# spi-adapter.net
KiCad netlist of a schematic drawn in EAGLE
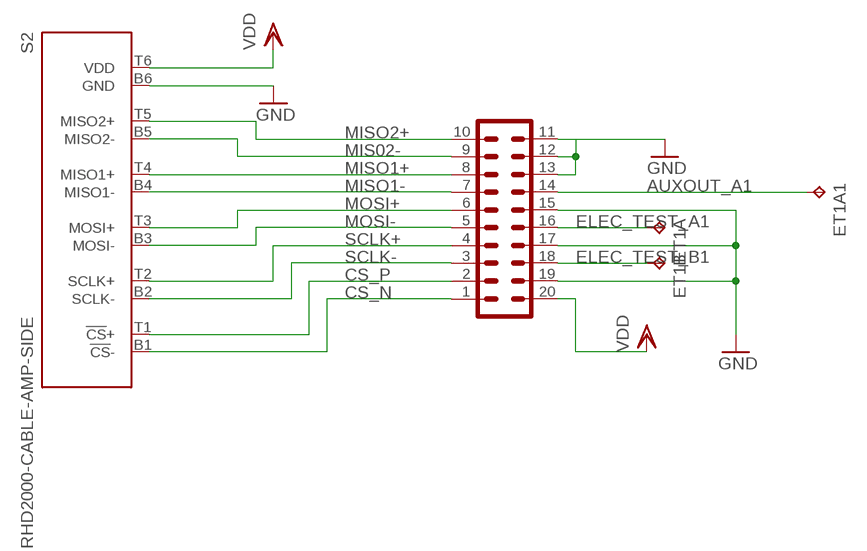
[diagram p0: schematic, sheet 1]

(export (version "E")
  (design (tool "Eeschema 10.0.6"))
  (components
    (comp (ref "ET1A")
      (value "TPPAD1-13")
      (footprint "eagle-import:P1-13")
      (libsource (lib "eagle-import") (part "TPPAD1-13"))
    )
    (comp (ref "ET1A1")
      (value "TPPAD1-13")
      (footprint "eagle-import:P1-13")
      (libsource (lib "eagle-import") (part "TPPAD1-13"))
    )
    (comp (ref "ET1B")
      (value "TPPAD1-13")
      (footprint "eagle-import:P1-13")
      (libsource (lib "eagle-import") (part "TPPAD1-13"))
    )
    (comp (ref "HS1")
      (value "JMD20-V")
      (footprint "eagle-import:JMD20-V")
      (libsource (lib "eagle-import") (part "PINHD-2X10_JMD20-V"))
    )
    (comp (ref "S2")
      (value "RHD2000-CABLE-AMP-SIDE")
      (footprint "eagle-import:OMNETICS_PZN-12-AA")
      (libsource (lib "eagle-import") (part "RHD2000-CABLE-AMP-SIDE"))
    )
  )
  (nets
    (net (code "1") (name "/AUXOUT_A1") (class "Default")
      (node (ref "ET1A1") (pin "TP") (pinfunction "TP_TP") (pintype "input"))
      (node (ref "HS1") (pin "14") (pinfunction "14_14") (pintype "bidirectional"))
    )
    (net (code "2") (name "/CS_N") (class "Default")
      (node (ref "HS1") (pin "1") (pinfunction "1_1") (pintype "bidirectional"))
      (node (ref "S2") (pin "B1") (pinfunction "~{CS}-_B1") (pintype "bidirectional"))
    )
    (net (code "3") (name "/CS_P") (class "Default")
      (node (ref "HS1") (pin "2") (pinfunction "2_2") (pintype "bidirectional"))
      (node (ref "S2") (pin "T1") (pinfunction "~{CS}+_T1") (pintype "bidirectional"))
    )
    (net (code "4") (name "/ELEC_TEST_A1") (class "Default")
      (node (ref "ET1A") (pin "TP") (pinfunction "TP_TP") (pintype "input"))
      (node (ref "HS1") (pin "16") (pinfunction "16_16") (pintype "bidirectional"))
    )
    (net (code "5") (name "/ELEC_TEST_B1") (class "Default")
      (node (ref "ET1B") (pin "TP") (pinfunction "TP_TP") (pintype "input"))
      (node (ref "HS1") (pin "18") (pinfunction "18_18") (pintype "bidirectional"))
    )
    (net (code "6") (name "/MIS02-") (class "Default")
      (node (ref "HS1") (pin "9") (pinfunction "9_9") (pintype "bidirectional"))
      (node (ref "S2") (pin "B5") (pinfunction "MISO2-_B5") (pintype "bidirectional"))
    )
    (net (code "7") (name "/MISO1+") (class "Default")
      (node (ref "HS1") (pin "8") (pinfunction "8_8") (pintype "bidirectional"))
      (node (ref "S2") (pin "T4") (pinfunction "MISO1+_T4") (pintype "bidirectional"))
    )
    (net (code "8") (name "/MISO1-") (class "Default")
      (node (ref "HS1") (pin "7") (pinfunction "7_7") (pintype "bidirectional"))
      (node (ref "S2") (pin "B4") (pinfunction "MISO1-_B4") (pintype "bidirectional"))
    )
    (net (code "9") (name "/MISO2+") (class "Default")
      (node (ref "HS1") (pin "10") (pinfunction "10_10") (pintype "bidirectional"))
      (node (ref "S2") (pin "T5") (pinfunction "MISO2+_T5") (pintype "bidirectional"))
    )
    (net (code "10") (name "/MOSI+") (class "Default")
      (node (ref "HS1") (pin "6") (pinfunction "6_6") (pintype "bidirectional"))
      (node (ref "S2") (pin "T3") (pinfunction "MOSI+_T3") (pintype "bidirectional"))
    )
    (net (code "11") (name "/MOSI-") (class "Default")
      (node (ref "HS1") (pin "5") (pinfunction "5_5") (pintype "bidirectional"))
      (node (ref "S2") (pin "B3") (pinfunction "MOSI-_B3") (pintype "bidirectional"))
    )
    (net (code "12") (name "/SCLK+") (class "Default")
      (node (ref "HS1") (pin "4") (pinfunction "4_4") (pintype "bidirectional"))
      (node (ref "S2") (pin "T2") (pinfunction "SCLK+_T2") (pintype "bidirectional"))
    )
    (net (code "13") (name "/SCLK-") (class "Default")
      (node (ref "HS1") (pin "3") (pinfunction "3_3") (pintype "bidirectional"))
      (node (ref "S2") (pin "B2") (pinfunction "SCLK-_B2") (pintype "bidirectional"))
    )
    (net (code "14") (name "GND") (class "Default")
      (node (ref "HS1") (pin "11") (pinfunction "11_11") (pintype "bidirectional"))
      (node (ref "HS1") (pin "12") (pinfunction "12_12") (pintype "bidirectional"))
      (node (ref "HS1") (pin "13") (pinfunction "13_13") (pintype "bidirectional"))
      (node (ref "HS1") (pin "15") (pinfunction "15_15") (pintype "bidirectional"))
      (node (ref "HS1") (pin "17") (pinfunction "17_17") (pintype "bidirectional"))
      (node (ref "HS1") (pin "19") (pinfunction "19_19") (pintype "bidirectional"))
      (node (ref "S2") (pin "B6") (pinfunction "GND_B6") (pintype "power_in"))
    )
    (net (code "15") (name "VDD") (class "Default")
      (node (ref "HS1") (pin "20") (pinfunction "20_20") (pintype "bidirectional"))
      (node (ref "S2") (pin "T6") (pinfunction "VDD_T6") (pintype "bidirectional"))
    )
  )
)
